# MICRO-GRUPO_5-5A_schDoc.net
KiCad netlist of a schematic drawn in Altium Designer
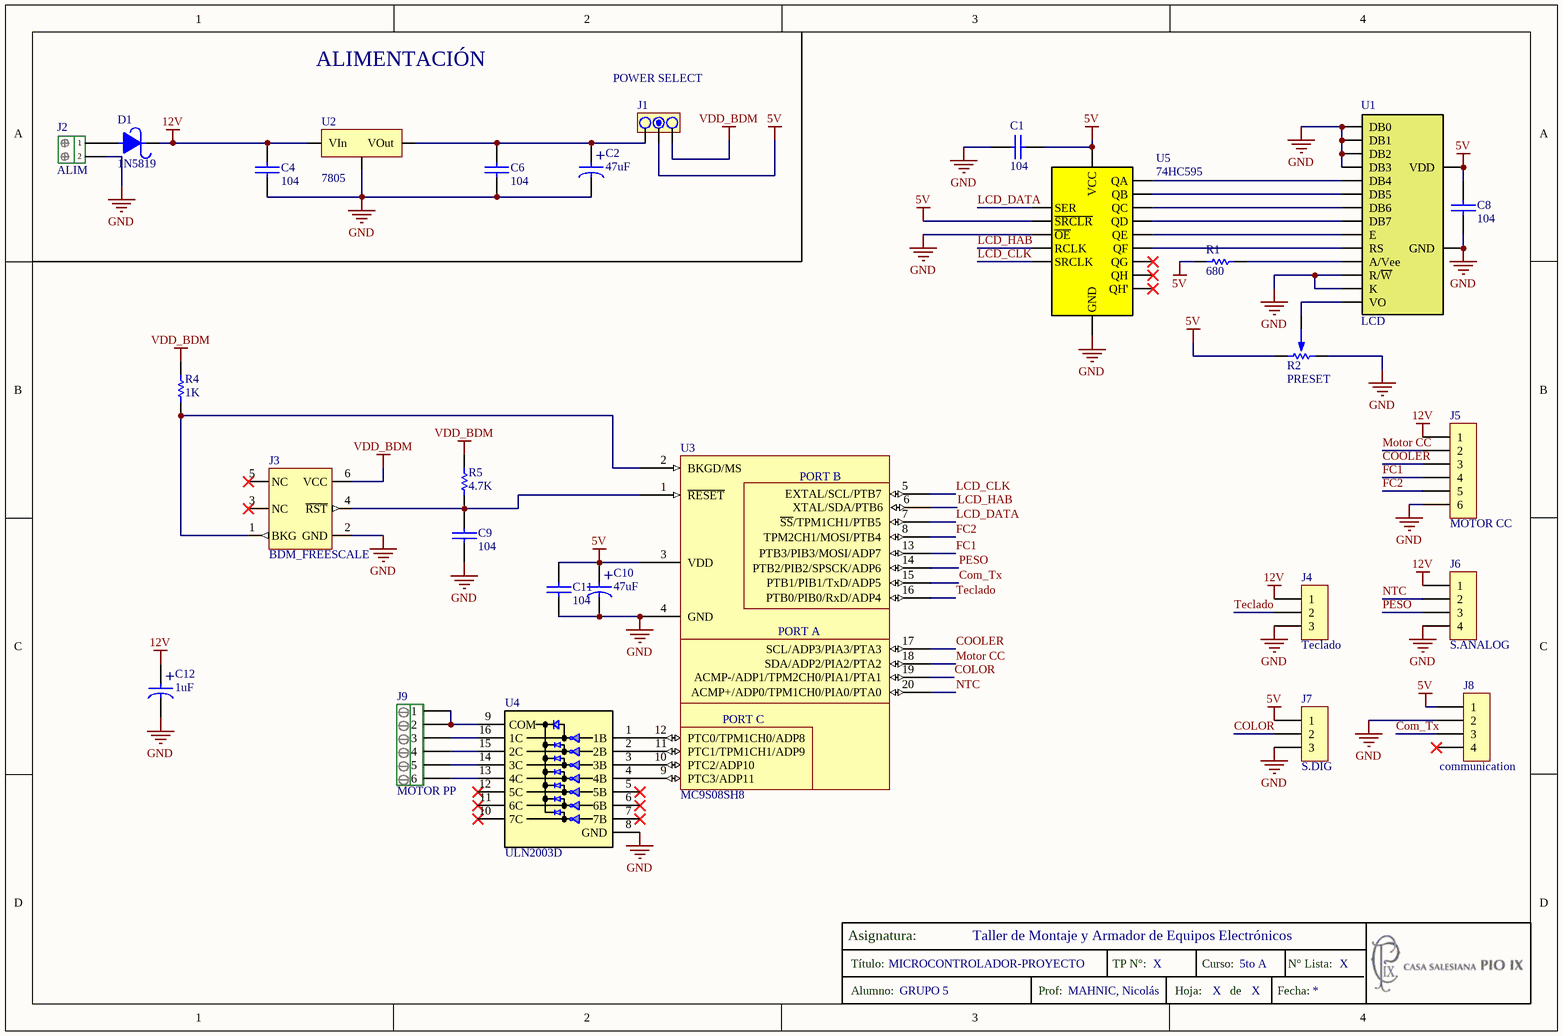
[diagram p0: MICRO-GRUPO_5-5A.schDoc.SchDoc]

(export (version "E")
  (design (tool "Eeschema 10.0.6"))
  (components
    (comp (ref "C1")
      (value "104")
      (footprint "0805")
      (description "cap")
      (fields (field (name "AUTOR") "Guido Spataro"))
      (libsource (lib "simbolo") (part "CAP"))
    )
    (comp (ref "C2")
      (value "47uF")
      (footprint "Capol")
      (description "Cap polarizado")
      (libsource (lib "simbolo") (part "CAPPOL"))
    )
    (comp (ref "C4")
      (value "104")
      (footprint "0805")
      (description "cap")
      (fields (field (name "AUTOR") "Guido Spataro"))
      (libsource (lib "simbolo") (part "CAP"))
    )
    (comp (ref "C6")
      (value "104")
      (footprint "0805")
      (description "cap")
      (fields (field (name "AUTOR") "Guido Spataro"))
      (libsource (lib "simbolo") (part "CAP"))
    )
    (comp (ref "C8")
      (value "104")
      (footprint "0805")
      (description "cap")
      (fields (field (name "AUTOR") "Guido Spataro"))
      (libsource (lib "simbolo") (part "CAP"))
    )
    (comp (ref "C9")
      (value "104")
      (footprint "0805")
      (description "cap")
      (fields (field (name "AUTOR") "Guido Spataro"))
      (libsource (lib "simbolo") (part "CAP"))
    )
    (comp (ref "C10")
      (value "47uF")
      (footprint "Capol")
      (description "Cap polarizado")
      (libsource (lib "simbolo") (part "CAPPOL"))
    )
    (comp (ref "C11")
      (value "104")
      (footprint "0805")
      (description "cap")
      (fields (field (name "AUTOR") "Guido Spataro"))
      (libsource (lib "simbolo") (part "CAP"))
    )
    (comp (ref "C12")
      (value "1uF")
      (footprint "Capol")
      (description "Cap polarizado")
      (libsource (lib "simbolo") (part "CAPPOL"))
    )
    (comp (ref "D1")
      (value "1N5819")
      (footprint "Diodo")
      (description "Diodo")
      (fields (field (name "AUTOR") "Guido Spataro"))
      (libsource (lib "simbolo") (part "DIODO SCHOTTKY"))
    )
    (comp (ref "J1")
      (value "POWER SELECT")
      (footprint "JUMPER_3")
      (description "Jumper")
      (fields (field (name "AUTOR") "Guido Spataro"))
      (libsource (lib "simbolo") (part "JUMPER_3"))
    )
    (comp (ref "J2")
      (value "ALIM")
      (footprint "BORNERA2")
      (description "Bornera de 2 pines")
      (fields (field (name "AUTOR") "Guido Spataro"))
      (libsource (lib "simbolo") (part "Bornera_2"))
    )
    (comp (ref "J3")
      (value "BDM_FREESCALE")
      (footprint "SIP3*2")
      (description "BDM")
      (fields (field (name "AUTOR") "Guido Spataro"))
      (libsource (lib "simbolo") (part "BDM"))
    )
    (comp (ref "J4") (value "Teclado") (footprint "SIP3 90") (libsource (lib "simbolo") (part "CON3")))
    (comp (ref "J5") (value "MOTOR CC") (footprint "SIP6") (libsource (lib "simbolo") (part "CON6")))
    (comp (ref "J6") (value "S.ANALOG") (footprint "SIP4 90") (libsource (lib "simbolo") (part "CON4")))
    (comp (ref "J7") (value "S.DIG") (footprint "SIP3 90") (libsource (lib "simbolo") (part "CON3")))
    (comp (ref "J8") (value "communication") (footprint "SIP4 90") (libsource (lib "simbolo") (part "CON4")))
    (comp (ref "J9")
      (value "MOTOR PP")
      (footprint "BORNERA6")
      (description "current output")
      (fields (field (name "AUTOR") "MARTINEZ Agustin"))
      (libsource (lib "simbolo") (part "BORNERA 6"))
    )
    (comp (ref "R1")
      (value "680")
      (footprint "0805")
      (description "Resistencia")
      (fields (field (name "AUTOR") "Guido Spataro"))
      (libsource (lib "simbolo") (part "RES"))
    )
    (comp (ref "R2") (value "PRESET") (footprint "PRESET H") (libsource (lib "simbolo") (part "PRESET")))
    (comp (ref "R4")
      (value "1K")
      (footprint "0805")
      (description "Resistencia")
      (fields (field (name "AUTOR") "Guido Spataro"))
      (libsource (lib "simbolo") (part "RES"))
    )
    (comp (ref "R5")
      (value "4.7K")
      (footprint "0805")
      (description "Resistencia")
      (fields (field (name "AUTOR") "Guido Spataro"))
      (libsource (lib "simbolo") (part "RES"))
    )
    (comp (ref "U1") (value "LCD") (footprint "LCD") (libsource (lib "simbolo") (part "LCD 16*4")))
    (comp (ref "U2")
      (value "7805")
      (footprint "TO-220 V")
      (description "REGULDOR POSITIVO")
      (libsource (lib "simbolo") (part "78XX"))
    )
    (comp (ref "U3")
      (value "MC9S08SH8")
      (footprint "DIP20")
      (description "Micro controlador")
      (fields (field (name "AUTOR") "Guido Spataro"))
      (libsource (lib "simbolo") (part "MC9S08SH8"))
    )
    (comp (ref "U4")
      (value "ULN2003D")
      (footprint "SOIC16")
      (description "Controlador de corriente")
      (fields (field (name "AUTOR") "MARTINEZ Agustin"))
      (libsource (lib "simbolo") (part "ULN2003D"))
    )
    (comp (ref "U5") (value "74HC595") (footprint "74hc595_v2") (libsource (lib "simbolo") (part "74HC595")))
  )
  (nets
    (net (code "1") (name "/COLOR") (class "Default")
      (node (ref "J7") (pin "2") (pinfunction "2_2") (pintype "passive"))
      (node (ref "U3") (pin "19") (pinfunction "ACMP-/ADP1/TPM2CH0/PIA1/PTA1_19") (pintype "bidirectional"))
    )
    (net (code "2") (name "/COOLER") (class "Default")
      (node (ref "J5") (pin "3") (pinfunction "3_3") (pintype "passive"))
      (node (ref "U3") (pin "17") (pinfunction "SCL/ADP3/PIA3/PTA3_17") (pintype "bidirectional"))
    )
    (net (code "3") (name "/Com_Tx") (class "Default")
      (node (ref "J8") (pin "3") (pinfunction "3_3") (pintype "passive"))
      (node (ref "U3") (pin "15") (pinfunction "PTB1/PIB1/TxD/ADP5_15") (pintype "bidirectional"))
    )
    (net (code "4") (name "/FC1") (class "Default")
      (node (ref "J5") (pin "4") (pinfunction "4_4") (pintype "passive"))
      (node (ref "U3") (pin "13") (pinfunction "PTB3/PIB3/MOSI/ADP7_13") (pintype "bidirectional"))
    )
    (net (code "5") (name "/FC2") (class "Default")
      (node (ref "J5") (pin "5") (pinfunction "5_5") (pintype "passive"))
      (node (ref "U3") (pin "8") (pinfunction "TPM2CH1/MOSI/PTB4_8") (pintype "bidirectional"))
    )
    (net (code "6") (name "/LCD_CLK") (class "Default")
      (node (ref "U3") (pin "5") (pinfunction "EXTAL/SCL/PTB7_5") (pintype "bidirectional"))
      (node (ref "U5") (pin "11") (pinfunction "SRCLK_11") (pintype "passive"))
    )
    (net (code "7") (name "/LCD_DATA") (class "Default")
      (node (ref "U3") (pin "7") (pinfunction "~{SS}/TPM1CH1/PTB5_7") (pintype "bidirectional"))
      (node (ref "U5") (pin "14") (pinfunction "SER_14") (pintype "passive"))
    )
    (net (code "8") (name "/LCD_HAB") (class "Default")
      (node (ref "U3") (pin "6") (pinfunction "XTAL/SDA/PTB6_6") (pintype "bidirectional"))
      (node (ref "U5") (pin "12") (pinfunction "RCLK_12") (pintype "passive"))
    )
    (net (code "9") (name "/Motor CC") (class "Default")
      (node (ref "J5") (pin "2") (pinfunction "2_2") (pintype "passive"))
      (node (ref "U3") (pin "18") (pinfunction "SDA/ADP2/PIA2/PTA2_18") (pintype "bidirectional"))
    )
    (net (code "10") (name "/NTC") (class "Default")
      (node (ref "J6") (pin "2") (pinfunction "2_2") (pintype "passive"))
      (node (ref "U3") (pin "20") (pinfunction "ACMP+/ADP0/TPM1CH0/PIA0/PTA0_20") (pintype "bidirectional"))
    )
    (net (code "11") (name "/PESO") (class "Default")
      (node (ref "J6") (pin "3") (pinfunction "3_3") (pintype "passive"))
      (node (ref "U3") (pin "14") (pinfunction "PTB2/PIB2/SPSCK/ADP6_14") (pintype "bidirectional"))
    )
    (net (code "12") (name "/Teclado") (class "Default")
      (node (ref "J4") (pin "2") (pinfunction "2_2") (pintype "passive"))
      (node (ref "U3") (pin "16") (pinfunction "PTB0/PIB0/RxD/ADP4_16") (pintype "bidirectional"))
    )
    (net (code "13") (name "5V") (class "Default")
      (node (ref "C1") (pin "2") (pinfunction "2_2") (pintype "passive"))
      (node (ref "C10") (pin "1") (pinfunction "1_1") (pintype "passive"))
      (node (ref "C11") (pin "1") (pinfunction "1_1") (pintype "passive"))
      (node (ref "C8") (pin "2") (pinfunction "2_2") (pintype "passive"))
      (node (ref "J1") (pin "2") (pinfunction "2_2") (pintype "passive"))
      (node (ref "J7") (pin "1") (pinfunction "1_1") (pintype "passive"))
      (node (ref "J8") (pin "1") (pinfunction "1_1") (pintype "passive"))
      (node (ref "R1") (pin "2") (pinfunction "2_2") (pintype "passive"))
      (node (ref "R2") (pin "1") (pinfunction "1_1") (pintype "passive"))
      (node (ref "U1") (pin "2") (pinfunction "VDD_2") (pintype "passive"))
      (node (ref "U3") (pin "3") (pinfunction "VDD_3") (pintype "passive"))
      (node (ref "U5") (pin "10") (pinfunction "~{SRCLR}_10") (pintype "passive"))
      (node (ref "U5") (pin "16") (pinfunction "VCC_16") (pintype "passive"))
    )
    (net (code "14") (name "12V") (class "Default")
      (node (ref "C12") (pin "1") (pinfunction "1_1") (pintype "passive"))
      (node (ref "C4") (pin "1") (pinfunction "1_1") (pintype "passive"))
      (node (ref "D1") (pin "2") (pinfunction "2_2") (pintype "passive"))
      (node (ref "J4") (pin "1") (pinfunction "1_1") (pintype "passive"))
      (node (ref "J5") (pin "1") (pinfunction "1_1") (pintype "passive"))
      (node (ref "J6") (pin "1") (pinfunction "1_1") (pintype "passive"))
      (node (ref "U2") (pin "1") (pinfunction "VIn_1") (pintype "passive"))
    )
    (net (code "15") (name "GND") (class "Default")
      (node (ref "C1") (pin "1") (pinfunction "1_1") (pintype "passive"))
      (node (ref "C10") (pin "2") (pinfunction "2_2") (pintype "passive"))
      (node (ref "C11") (pin "2") (pinfunction "2_2") (pintype "passive"))
      (node (ref "C12") (pin "2") (pinfunction "2_2") (pintype "passive"))
      (node (ref "C2") (pin "2") (pinfunction "2_2") (pintype "passive"))
      (node (ref "C4") (pin "2") (pinfunction "2_2") (pintype "passive"))
      (node (ref "C6") (pin "2") (pinfunction "2_2") (pintype "passive"))
      (node (ref "C8") (pin "1") (pinfunction "1_1") (pintype "passive"))
      (node (ref "C9") (pin "2") (pinfunction "2_2") (pintype "passive"))
      (node (ref "J2") (pin "2") (pinfunction "2_2") (pintype "passive"))
      (node (ref "J3") (pin "2") (pinfunction "GND_2") (pintype "passive"))
      (node (ref "J4") (pin "3") (pinfunction "3_3") (pintype "passive"))
      (node (ref "J5") (pin "6") (pinfunction "6_6") (pintype "passive"))
      (node (ref "J6") (pin "4") (pinfunction "4_4") (pintype "passive"))
      (node (ref "J7") (pin "3") (pinfunction "3_3") (pintype "passive"))
      (node (ref "J8") (pin "2") (pinfunction "2_2") (pintype "passive"))
      (node (ref "R2") (pin "3") (pinfunction "3_3") (pintype "passive"))
      (node (ref "U1") (pin "1") (pinfunction "GND_1") (pintype "passive"))
      (node (ref "U1") (pin "10") (pinfunction "DB3_10") (pintype "passive"))
      (node (ref "U1") (pin "16") (pinfunction "K_16") (pintype "passive"))
      (node (ref "U1") (pin "5") (pinfunction "R/~{W}_5") (pintype "passive"))
      (node (ref "U1") (pin "7") (pinfunction "DB0_7") (pintype "passive"))
      (node (ref "U1") (pin "8") (pinfunction "DB1_8") (pintype "passive"))
      (node (ref "U1") (pin "9") (pinfunction "DB2_9") (pintype "passive"))
      (node (ref "U2") (pin "2") (pinfunction "GND_2") (pintype "passive"))
      (node (ref "U3") (pin "4") (pinfunction "GND_4") (pintype "passive"))
      (node (ref "U4") (pin "8") (pinfunction "GND_8") (pintype "passive"))
      (node (ref "U5") (pin "13") (pinfunction "~{OE}_13") (pintype "passive"))
      (node (ref "U5") (pin "8") (pinfunction "GND_8") (pintype "passive"))
    )
    (net (code "16") (name "Net-(D1-Pad1)") (class "Default")
      (node (ref "D1") (pin "1") (pinfunction "1_1") (pintype "passive"))
      (node (ref "J2") (pin "1") (pinfunction "1_1") (pintype "passive"))
    )
    (net (code "17") (name "Net-(J3-BKG)") (class "Default")
      (node (ref "J3") (pin "1") (pinfunction "BKG_1") (pintype "output"))
      (node (ref "R4") (pin "1") (pinfunction "1_1") (pintype "passive"))
      (node (ref "U3") (pin "2") (pinfunction "BKGD/MS_2") (pintype "input"))
    )
    (net (code "18") (name "Net-(J3-~{RST})") (class "Default")
      (node (ref "C9") (pin "1") (pinfunction "1_1") (pintype "passive"))
      (node (ref "J3") (pin "4") (pinfunction "~{RST}_4") (pintype "output"))
      (node (ref "R5") (pin "1") (pinfunction "1_1") (pintype "passive"))
      (node (ref "U3") (pin "1") (pinfunction "~{RESET}_1") (pintype "input"))
    )
    (net (code "19") (name "Net-(U1-A{slash}Vee)") (class "Default")
      (node (ref "R1") (pin "1") (pinfunction "1_1") (pintype "passive"))
      (node (ref "U1") (pin "15") (pinfunction "A/Vee_15") (pintype "passive"))
    )
    (net (code "20") (name "Net-(U1-DB4)") (class "Default")
      (node (ref "U1") (pin "11") (pinfunction "DB4_11") (pintype "passive"))
      (node (ref "U5") (pin "15") (pinfunction "QA_15") (pintype "passive"))
    )
    (net (code "21") (name "Net-(U1-DB5)") (class "Default")
      (node (ref "U1") (pin "12") (pinfunction "DB5_12") (pintype "passive"))
      (node (ref "U5") (pin "1") (pinfunction "QB_1") (pintype "passive"))
    )
    (net (code "22") (name "Net-(U1-DB6)") (class "Default")
      (node (ref "U1") (pin "13") (pinfunction "DB6_13") (pintype "passive"))
      (node (ref "U5") (pin "2") (pinfunction "QC_2") (pintype "passive"))
    )
    (net (code "23") (name "Net-(U1-DB7)") (class "Default")
      (node (ref "U1") (pin "14") (pinfunction "DB7_14") (pintype "passive"))
      (node (ref "U5") (pin "3") (pinfunction "QD_3") (pintype "passive"))
    )
    (net (code "24") (name "Net-(U1-E)") (class "Default")
      (node (ref "U1") (pin "6") (pinfunction "E_6") (pintype "passive"))
      (node (ref "U5") (pin "4") (pinfunction "QE_4") (pintype "passive"))
    )
    (net (code "25") (name "Net-(U1-RS)") (class "Default")
      (node (ref "U1") (pin "4") (pinfunction "RS_4") (pintype "passive"))
      (node (ref "U5") (pin "5") (pinfunction "QF_5") (pintype "passive"))
    )
    (net (code "26") (name "Net-(U1-VO)") (class "Default")
      (node (ref "R2") (pin "2") (pinfunction "2_2") (pintype "passive"))
      (node (ref "U1") (pin "3") (pinfunction "VO_3") (pintype "passive"))
    )
    (net (code "27") (name "Net-(U2-VOut)") (class "Default")
      (node (ref "C2") (pin "1") (pinfunction "1_1") (pintype "passive"))
      (node (ref "C6") (pin "1") (pinfunction "1_1") (pintype "passive"))
      (node (ref "J1") (pin "3") (pinfunction "3_3") (pintype "passive"))
      (node (ref "U2") (pin "3") (pinfunction "VOut_3") (pintype "passive"))
    )
    (net (code "28") (name "Net-(U3-PTC0{slash}TPM1CH0{slash}ADP8)") (class "Default")
      (node (ref "U3") (pin "12") (pinfunction "PTC0/TPM1CH0/ADP8_12") (pintype "bidirectional"))
      (node (ref "U4") (pin "1") (pinfunction "1B_1") (pintype "passive"))
    )
    (net (code "29") (name "Net-(U3-PTC1{slash}TPM1CH1{slash}ADP9)") (class "Default")
      (node (ref "U3") (pin "11") (pinfunction "PTC1/TPM1CH1/ADP9_11") (pintype "bidirectional"))
      (node (ref "U4") (pin "2") (pinfunction "2B_2") (pintype "passive"))
    )
    (net (code "30") (name "Net-(U3-PTC2{slash}ADP10)") (class "Default")
      (node (ref "U3") (pin "10") (pinfunction "PTC2/ADP10_10") (pintype "bidirectional"))
      (node (ref "U4") (pin "3") (pinfunction "3B_3") (pintype "passive"))
    )
    (net (code "31") (name "Net-(U3-PTC3{slash}ADP11)") (class "Default")
      (node (ref "U3") (pin "9") (pinfunction "PTC3/ADP11_9") (pintype "bidirectional"))
      (node (ref "U4") (pin "4") (pinfunction "4B_4") (pintype "passive"))
    )
    (net (code "32") (name "Net-(U4-1C)") (class "Default")
      (node (ref "J9") (pin "3") (pinfunction "3_3") (pintype "passive"))
      (node (ref "U4") (pin "16") (pinfunction "1C_16") (pintype "passive"))
    )
    (net (code "33") (name "Net-(U4-2C)") (class "Default")
      (node (ref "J9") (pin "4") (pinfunction "4_4") (pintype "passive"))
      (node (ref "U4") (pin "15") (pinfunction "2C_15") (pintype "passive"))
    )
    (net (code "34") (name "Net-(U4-3C)") (class "Default")
      (node (ref "J9") (pin "5") (pinfunction "5_5") (pintype "passive"))
      (node (ref "U4") (pin "14") (pinfunction "3C_14") (pintype "passive"))
    )
    (net (code "35") (name "Net-(U4-4C)") (class "Default")
      (node (ref "J9") (pin "6") (pinfunction "6_6") (pintype "passive"))
      (node (ref "U4") (pin "13") (pinfunction "4C_13") (pintype "passive"))
    )
    (net (code "36") (name "Net-(U4-COM)") (class "Default")
      (node (ref "J9") (pin "1") (pinfunction "1_1") (pintype "passive"))
      (node (ref "J9") (pin "2") (pinfunction "2_2") (pintype "passive"))
      (node (ref "U4") (pin "9") (pinfunction "COM_9") (pintype "passive"))
    )
    (net (code "37") (name "VDD_BDM") (class "Default")
      (node (ref "J1") (pin "1") (pinfunction "1_1") (pintype "passive"))
      (node (ref "J3") (pin "6") (pinfunction "VCC_6") (pintype "passive"))
      (node (ref "R4") (pin "2") (pinfunction "2_2") (pintype "passive"))
      (node (ref "R5") (pin "2") (pinfunction "2_2") (pintype "passive"))
    )
    (net (code "38") (name "unconnected-(J3-NC-Pad3)") (class "Default")
      (node (ref "J3") (pin "3") (pinfunction "NC_3") (pintype "passive+no_connect"))
    )
    (net (code "39") (name "unconnected-(J3-NC-Pad5)") (class "Default")
      (node (ref "J3") (pin "5") (pinfunction "NC_5") (pintype "passive+no_connect"))
    )
    (net (code "40") (name "unconnected-(J8-Pad4)") (class "Default")
      (node (ref "J8") (pin "4") (pinfunction "4_4") (pintype "passive+no_connect"))
    )
    (net (code "41") (name "unconnected-(U4-5B-Pad5)") (class "Default")
      (node (ref "U4") (pin "5") (pinfunction "5B_5") (pintype "passive+no_connect"))
    )
    (net (code "42") (name "unconnected-(U4-5C-Pad12)") (class "Default")
      (node (ref "U4") (pin "12") (pinfunction "5C_12") (pintype "passive+no_connect"))
    )
    (net (code "43") (name "unconnected-(U4-6B-Pad6)") (class "Default")
      (node (ref "U4") (pin "6") (pinfunction "6B_6") (pintype "passive+no_connect"))
    )
    (net (code "44") (name "unconnected-(U4-6C-Pad11)") (class "Default")
      (node (ref "U4") (pin "11") (pinfunction "6C_11") (pintype "passive+no_connect"))
    )
    (net (code "45") (name "unconnected-(U4-7B-Pad7)") (class "Default")
      (node (ref "U4") (pin "7") (pinfunction "7B_7") (pintype "passive+no_connect"))
    )
    (net (code "46") (name "unconnected-(U4-7C-Pad10)") (class "Default")
      (node (ref "U4") (pin "10") (pinfunction "7C_10") (pintype "passive+no_connect"))
    )
    (net (code "47") (name "unconnected-(U5-QG-Pad6)") (class "Default")
      (node (ref "U5") (pin "6") (pinfunction "QG_6") (pintype "passive+no_connect"))
    )
    (net (code "48") (name "unconnected-(U5-QH'-Pad9)") (class "Default")
      (node (ref "U5") (pin "9") (pinfunction "QH'_9") (pintype "passive+no_connect"))
    )
    (net (code "49") (name "unconnected-(U5-QH-Pad7)") (class "Default")
      (node (ref "U5") (pin "7") (pinfunction "QH_7") (pintype "passive+no_connect"))
    )
  )
)
